# dice_595.net
KiCad netlist of a schematic drawn in EAGLE
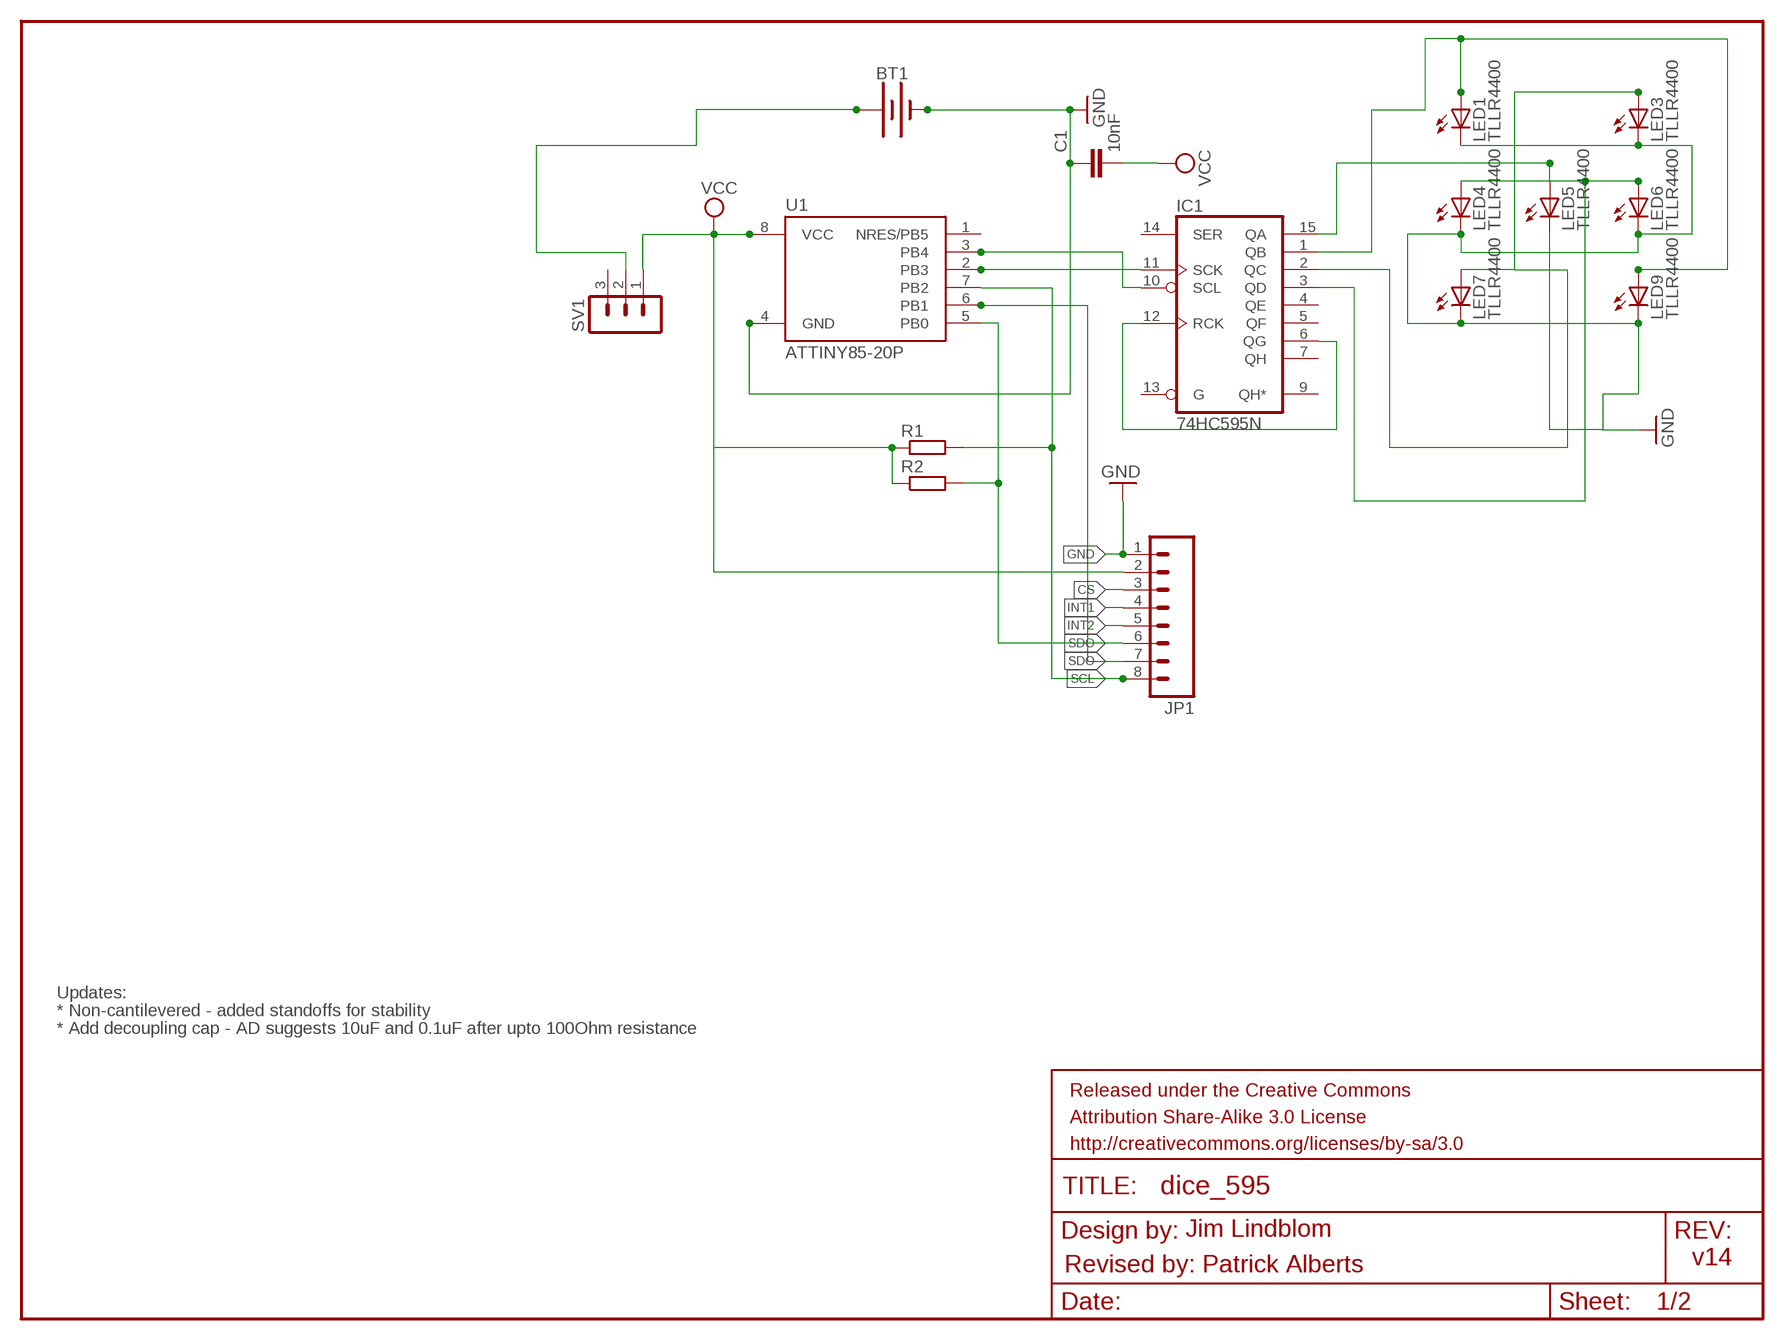
[diagram p0: schematic, sheet 1]

(export (version "E")
  (design (tool "Eeschema 10.0.6"))
  (components
    (comp (ref "BT1")
      (value "BATTERY-20MM_PTH")
      (footprint "eagle-import:BATTCOM_20MM_PTH")
      (libsource (lib "eagle-import") (part "BATTERY-20MM_PTH"))
    )
    (comp (ref "C1")
      (value "10nF")
      (footprint "eagle-import:C025-024X044")
      (libsource (lib "eagle-import") (part "C-EU025-024X044"))
    )
    (comp (ref "IC1")
      (value "74HC595N")
      (footprint "eagle-import:DIL16")
      (libsource (lib "eagle-import") (part "74595NHC"))
    )
    (comp (ref "JP1")
      (value "M08")
      (footprint "eagle-import:1X08")
      (libsource (lib "eagle-import") (part "M08"))
    )
    (comp (ref "LED1")
      (value "TLLR4400")
      (footprint "eagle-import:LED3MM")
      (fields (field (name "MF") "VISHAY SEMICONDUCTOR"))
      (libsource (lib "eagle-import") (part "TLLR4400"))
    )
    (comp (ref "LED3")
      (value "TLLR4400")
      (footprint "eagle-import:LED3MM")
      (fields (field (name "MF") "VISHAY SEMICONDUCTOR"))
      (libsource (lib "eagle-import") (part "TLLR4400"))
    )
    (comp (ref "LED4")
      (value "TLLR4400")
      (footprint "eagle-import:LED3MM")
      (fields (field (name "MF") "VISHAY SEMICONDUCTOR"))
      (libsource (lib "eagle-import") (part "TLLR4400"))
    )
    (comp (ref "LED5")
      (value "TLLR4400")
      (footprint "eagle-import:LED3MM")
      (fields (field (name "MF") "VISHAY SEMICONDUCTOR"))
      (libsource (lib "eagle-import") (part "TLLR4400"))
    )
    (comp (ref "LED6")
      (value "TLLR4400")
      (footprint "eagle-import:LED3MM")
      (fields (field (name "MF") "VISHAY SEMICONDUCTOR"))
      (libsource (lib "eagle-import") (part "TLLR4400"))
    )
    (comp (ref "LED7")
      (value "TLLR4400")
      (footprint "eagle-import:LED3MM")
      (fields (field (name "MF") "VISHAY SEMICONDUCTOR"))
      (libsource (lib "eagle-import") (part "TLLR4400"))
    )
    (comp (ref "LED9")
      (value "TLLR4400")
      (footprint "eagle-import:LED3MM")
      (fields (field (name "MF") "VISHAY SEMICONDUCTOR"))
      (libsource (lib "eagle-import") (part "TLLR4400"))
    )
    (comp (ref "R1")
      (value "R-EU_0207/12")
      (footprint "eagle-import:0207_12")
      (libsource (lib "eagle-import") (part "R-EU_0207/12"))
    )
    (comp (ref "R2")
      (value "R-EU_0207/2V")
      (footprint "eagle-import:0207_2V")
      (libsource (lib "eagle-import") (part "R-EU_0207/2V"))
    )
    (comp (ref "SV1")
      (value "MA03-1")
      (footprint "eagle-import:MA03-1")
      (libsource (lib "eagle-import") (part "MA03-1"))
    )
    (comp (ref "U1")
      (value "ATTINY85-20P")
      (footprint "eagle-import:PDIP08_300MIL")
      (libsource (lib "eagle-import") (part "ATTINY85P-20"))
    )
  )
  (nets
    (net (code "1") (name "CS") (class "Default")
      (node (ref "JP1") (pin "3") (pinfunction "3_3") (pintype "passive"))
    )
    (net (code "2") (name "GND") (class "Default")
      (node (ref "BT1") (pin "2") (pinfunction "-_2") (pintype "power_in"))
      (node (ref "C1") (pin "1") (pinfunction "1_1") (pintype "passive"))
      (node (ref "JP1") (pin "1") (pinfunction "1_1") (pintype "passive"))
      (node (ref "LED1") (pin "K") (pinfunction "C_K") (pintype "passive"))
      (node (ref "LED3") (pin "K") (pinfunction "C_K") (pintype "passive"))
      (node (ref "LED4") (pin "K") (pinfunction "C_K") (pintype "passive"))
      (node (ref "LED5") (pin "K") (pinfunction "C_K") (pintype "passive"))
      (node (ref "LED6") (pin "K") (pinfunction "C_K") (pintype "passive"))
      (node (ref "LED7") (pin "K") (pinfunction "C_K") (pintype "passive"))
      (node (ref "LED9") (pin "K") (pinfunction "C_K") (pintype "passive"))
      (node (ref "U1") (pin "4") (pinfunction "GND_4") (pintype "power_in"))
    )
    (net (code "3") (name "INT1") (class "Default")
      (node (ref "JP1") (pin "4") (pinfunction "4_4") (pintype "passive"))
    )
    (net (code "4") (name "INT2") (class "Default")
      (node (ref "JP1") (pin "5") (pinfunction "5_5") (pintype "passive"))
    )
    (net (code "5") (name "Net-(BT1-+)") (class "Default")
      (node (ref "BT1") (pin "1") (pinfunction "+_1") (pintype "power_in"))
      (node (ref "SV1") (pin "2") (pinfunction "2_2") (pintype "passive"))
    )
    (net (code "6") (name "Net-(IC1A-QA)") (class "Default")
      (node (ref "IC1") (pin "15") (pinfunction "QA_15") (pintype "tri_state"))
      (node (ref "LED5") (pin "A") (pinfunction "A_A") (pintype "passive"))
    )
    (net (code "7") (name "Net-(IC1A-QB)") (class "Default")
      (node (ref "IC1") (pin "1") (pinfunction "QB_1") (pintype "tri_state"))
      (node (ref "LED1") (pin "A") (pinfunction "A_A") (pintype "passive"))
      (node (ref "LED9") (pin "A") (pinfunction "A_A") (pintype "passive"))
    )
    (net (code "8") (name "Net-(IC1A-QC)") (class "Default")
      (node (ref "IC1") (pin "2") (pinfunction "QC_2") (pintype "tri_state"))
      (node (ref "LED3") (pin "A") (pinfunction "A_A") (pintype "passive"))
      (node (ref "LED7") (pin "A") (pinfunction "A_A") (pintype "passive"))
    )
    (net (code "9") (name "Net-(IC1A-QD)") (class "Default")
      (node (ref "IC1") (pin "3") (pinfunction "QD_3") (pintype "tri_state"))
      (node (ref "LED4") (pin "A") (pinfunction "A_A") (pintype "passive"))
      (node (ref "LED6") (pin "A") (pinfunction "A_A") (pintype "passive"))
    )
    (net (code "10") (name "Net-(IC1A-QG)") (class "Default")
      (node (ref "IC1") (pin "12") (pinfunction "RCK_12") (pintype "input"))
      (node (ref "IC1") (pin "6") (pinfunction "QG_6") (pintype "tri_state"))
    )
    (net (code "11") (name "Net-(IC1A-SCK)") (class "Default")
      (node (ref "IC1") (pin "11") (pinfunction "SCK_11") (pintype "input"))
      (node (ref "U1") (pin "2") (pinfunction "PB3_2") (pintype "bidirectional"))
    )
    (net (code "12") (name "Net-(IC1A-SCL)") (class "Default")
      (node (ref "IC1") (pin "10") (pinfunction "SCL_10") (pintype "input"))
      (node (ref "U1") (pin "3") (pinfunction "PB4_3") (pintype "bidirectional"))
    )
    (net (code "13") (name "Net-(U1-PB0)") (class "Default")
      (node (ref "JP1") (pin "6") (pinfunction "6_6") (pintype "passive"))
      (node (ref "R2") (pin "2") (pinfunction "2_2") (pintype "passive"))
      (node (ref "U1") (pin "5") (pinfunction "PB0_5") (pintype "bidirectional"))
    )
    (net (code "14") (name "SCL") (class "Default")
      (node (ref "JP1") (pin "8") (pinfunction "8_8") (pintype "passive"))
      (node (ref "R1") (pin "2") (pinfunction "2_2") (pintype "passive"))
      (node (ref "U1") (pin "7") (pinfunction "PB2_7") (pintype "bidirectional"))
    )
    (net (code "15") (name "SDO") (class "Default")
      (node (ref "JP1") (pin "7") (pinfunction "7_7") (pintype "passive"))
      (node (ref "U1") (pin "6") (pinfunction "PB1_6") (pintype "bidirectional"))
    )
    (net (code "16") (name "VCC") (class "Default")
      (node (ref "C1") (pin "2") (pinfunction "2_2") (pintype "passive"))
      (node (ref "JP1") (pin "2") (pinfunction "2_2") (pintype "passive"))
      (node (ref "R1") (pin "1") (pinfunction "1_1") (pintype "passive"))
      (node (ref "R2") (pin "1") (pinfunction "1_1") (pintype "passive"))
      (node (ref "SV1") (pin "1") (pinfunction "1_1") (pintype "passive"))
      (node (ref "U1") (pin "8") (pinfunction "VCC_8") (pintype "power_in"))
    )
    (net (code "17") (name "unconnected-(IC1A-G-Pad13)") (class "Default")
      (node (ref "IC1") (pin "13") (pinfunction "G_13") (pintype "input"))
    )
    (net (code "18") (name "unconnected-(IC1A-QE-Pad4)") (class "Default")
      (node (ref "IC1") (pin "4") (pinfunction "QE_4") (pintype "tri_state"))
    )
    (net (code "19") (name "unconnected-(IC1A-QF-Pad5)") (class "Default")
      (node (ref "IC1") (pin "5") (pinfunction "QF_5") (pintype "tri_state"))
    )
    (net (code "20") (name "unconnected-(IC1A-QH*-Pad9)") (class "Default")
      (node (ref "IC1") (pin "9") (pinfunction "QH*_9") (pintype "tri_state"))
    )
    (net (code "21") (name "unconnected-(IC1A-QH-Pad7)") (class "Default")
      (node (ref "IC1") (pin "7") (pinfunction "QH_7") (pintype "tri_state"))
    )
    (net (code "22") (name "unconnected-(IC1A-SER-Pad14)") (class "Default")
      (node (ref "IC1") (pin "14") (pinfunction "SER_14") (pintype "input"))
    )
    (net (code "23") (name "unconnected-(SV1-Pad3)") (class "Default")
      (node (ref "SV1") (pin "3") (pinfunction "3_3") (pintype "passive"))
    )
    (net (code "24") (name "unconnected-(U1-NRES{slash}PB5-Pad1)") (class "Default")
      (node (ref "U1") (pin "1") (pinfunction "NRES/PB5_1") (pintype "bidirectional"))
    )
  )
)
